# Battery_Management_System.net
KiCad netlist of a schematic drawn in Altium Designer
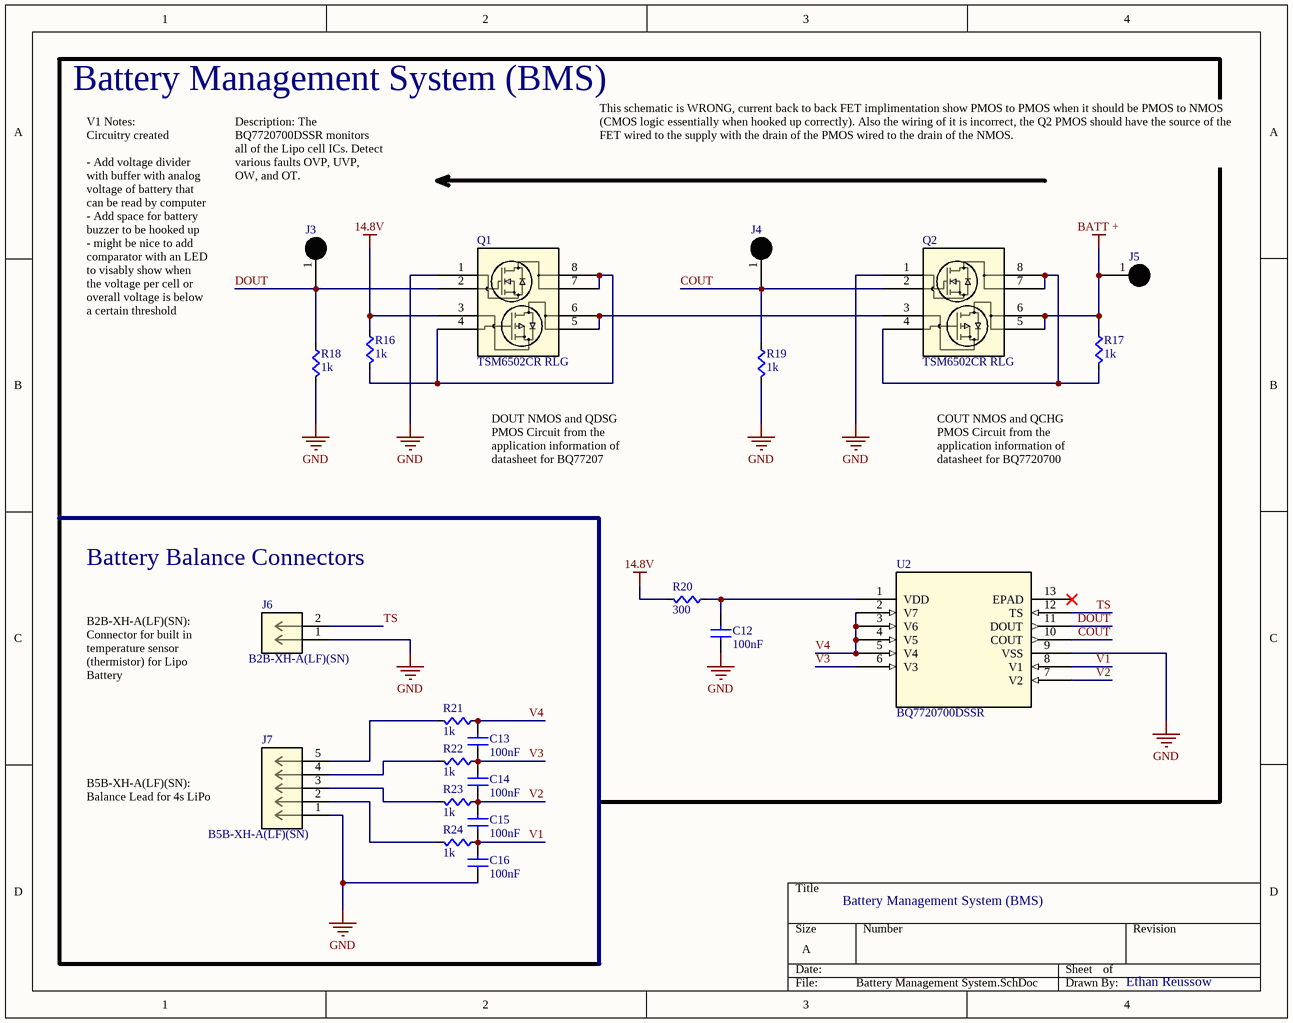
[diagram p0: Battery Management System.SchDoc]

(export (version "E")
  (design (tool "Eeschema 10.0.6"))
  (components
    (comp (ref "C12")
      (value "100nF")
      (footprint "CAPC0603")
      (fields (field (name "Comment") "Cap"))
      (libsource (lib "Passives") (part "Cap"))
    )
    (comp (ref "C13")
      (value "100nF")
      (footprint "CAPC0603")
      (fields (field (name "Comment") "Cap"))
      (libsource (lib "Passives") (part "Cap"))
    )
    (comp (ref "C14")
      (value "100nF")
      (footprint "CAPC0603")
      (fields (field (name "Comment") "Cap"))
      (libsource (lib "Passives") (part "Cap"))
    )
    (comp (ref "C15")
      (value "100nF")
      (footprint "CAPC0603")
      (fields (field (name "Comment") "Cap"))
      (libsource (lib "Passives") (part "Cap"))
    )
    (comp (ref "C16")
      (value "100nF")
      (footprint "CAPC0603")
      (fields (field (name "Comment") "Cap"))
      (libsource (lib "Passives") (part "Cap"))
    )
    (comp (ref "J3")
      (value "5000 Test Point")
      (footprint "5000 Test Point")
      (libsource (lib "Connectors") (part "5000 Test Point"))
    )
    (comp (ref "J4")
      (value "5000 Test Point")
      (footprint "5000 Test Point")
      (libsource (lib "Connectors") (part "5000 Test Point"))
    )
    (comp (ref "J5")
      (value "5000 Test Point")
      (footprint "5000 Test Point")
      (libsource (lib "Connectors") (part "5000 Test Point"))
    )
    (comp (ref "J6")
      (value "B2B-XH-A(LF)(SN)")
      (footprint "CONN_B2B-XH-A(LF)(SN)_JST")
      (description "No Description Available")
      (fields (field (name "COPYRIGHT") "Copyright (C) 2023 Ultra Librarian. All rights reserved."))
      (libsource (lib "Connectors") (part "B2B-XH-A(LF)(SN)"))
    )
    (comp (ref "J7")
      (value "B5B-XH-A(LF)(SN)")
      (footprint "CONN_B5B-XH-A(LF)(SN)_JST")
      (description "No Description Available")
      (fields (field (name "COPYRIGHT") "Copyright (C) 2023 Ultra Librarian. All rights reserved."))
      (libsource (lib "Connectors") (part "B5B-XH-A(LF)(SN)"))
    )
    (comp (ref "Q1")
      (value "TSM6502CR RLG")
      (footprint "PDFN56U_DUAL_TWS")
      (description "No Description Available")
      (fields (field (name "COPYRIGHT") "Copyright (C) 2023 Ultra Librarian. All rights reserved."))
      (libsource (lib "ICs") (part "TSM6502CR RLG"))
    )
    (comp (ref "Q2")
      (value "TSM6502CR RLG")
      (footprint "PDFN56U_DUAL_TWS")
      (description "No Description Available")
      (fields (field (name "COPYRIGHT") "Copyright (C) 2023 Ultra Librarian. All rights reserved."))
      (libsource (lib "ICs") (part "TSM6502CR RLG"))
    )
    (comp (ref "R16")
      (value "1k")
      (footprint "RES0603")
      (fields (field (name "Comment") "Res"))
      (libsource (lib "Passives") (part "Res"))
    )
    (comp (ref "R17")
      (value "1k")
      (footprint "RES0603")
      (fields (field (name "Comment") "Res"))
      (libsource (lib "Passives") (part "Res"))
    )
    (comp (ref "R18")
      (value "1k")
      (footprint "RES0603")
      (fields (field (name "Comment") "Res"))
      (libsource (lib "Passives") (part "Res"))
    )
    (comp (ref "R19")
      (value "1k")
      (footprint "RES0603")
      (fields (field (name "Comment") "Res"))
      (libsource (lib "Passives") (part "Res"))
    )
    (comp (ref "R20")
      (value "300")
      (footprint "RES0603")
      (fields (field (name "Comment") "Res"))
      (libsource (lib "Passives") (part "Res"))
    )
    (comp (ref "R21")
      (value "1k")
      (footprint "RES0603")
      (fields (field (name "Comment") "Res"))
      (libsource (lib "Passives") (part "Res"))
    )
    (comp (ref "R22")
      (value "1k")
      (footprint "RES0603")
      (fields (field (name "Comment") "Res"))
      (libsource (lib "Passives") (part "Res"))
    )
    (comp (ref "R23")
      (value "1k")
      (footprint "RES0603")
      (fields (field (name "Comment") "Res"))
      (libsource (lib "Passives") (part "Res"))
    )
    (comp (ref "R24")
      (value "1k")
      (footprint "RES0603")
      (fields (field (name "Comment") "Res"))
      (libsource (lib "Passives") (part "Res"))
    )
    (comp (ref "U2")
      (value "BQ7720700DSSR")
      (footprint "WSON12_DSS_TEX")
      (description "No Description Available")
      (fields (field (name "COPYRIGHT") "Copyright (C) 2023 Ultra Librarian. All rights reserved."))
      (libsource (lib "ICs") (part "BQ7720700DSSR"))
    )
  )
  (nets
    (net (code "1") (name "/COUT") (class "Default")
      (node (ref "J4") (pin "1") (pintype "passive"))
      (node (ref "Q2") (pin "2") (pinfunction "2_2") (pintype "passive"))
      (node (ref "R19") (pin "2") (pinfunction "B_2") (pintype "passive"))
      (node (ref "U2") (pin "10") (pinfunction "COUT_10") (pintype "output"))
    )
    (net (code "2") (name "/DOUT") (class "Default")
      (node (ref "J3") (pin "1") (pintype "passive"))
      (node (ref "Q1") (pin "2") (pinfunction "2_2") (pintype "passive"))
      (node (ref "R18") (pin "2") (pinfunction "B_2") (pintype "passive"))
      (node (ref "U2") (pin "11") (pinfunction "DOUT_11") (pintype "output"))
    )
    (net (code "3") (name "/TS") (class "Default")
      (node (ref "J6") (pin "2") (pinfunction "2_2") (pintype "passive"))
      (node (ref "U2") (pin "12") (pinfunction "TS_12") (pintype "input"))
    )
    (net (code "4") (name "/V1") (class "Default")
      (node (ref "C15") (pin "2") (pinfunction "B_2") (pintype "passive"))
      (node (ref "C16") (pin "1") (pinfunction "A_1") (pintype "passive"))
      (node (ref "R24") (pin "2") (pinfunction "B_2") (pintype "passive"))
      (node (ref "U2") (pin "8") (pinfunction "V1_8") (pintype "input"))
    )
    (net (code "5") (name "/V2") (class "Default")
      (node (ref "C14") (pin "2") (pinfunction "B_2") (pintype "passive"))
      (node (ref "C15") (pin "1") (pinfunction "A_1") (pintype "passive"))
      (node (ref "R23") (pin "2") (pinfunction "B_2") (pintype "passive"))
      (node (ref "U2") (pin "7") (pinfunction "V2_7") (pintype "input"))
    )
    (net (code "6") (name "/V3") (class "Default")
      (node (ref "C13") (pin "2") (pinfunction "B_2") (pintype "passive"))
      (node (ref "C14") (pin "1") (pinfunction "A_1") (pintype "passive"))
      (node (ref "R22") (pin "2") (pinfunction "B_2") (pintype "passive"))
      (node (ref "U2") (pin "6") (pinfunction "V3_6") (pintype "input"))
    )
    (net (code "7") (name "/V4") (class "Default")
      (node (ref "C13") (pin "1") (pinfunction "A_1") (pintype "passive"))
      (node (ref "R21") (pin "2") (pinfunction "B_2") (pintype "passive"))
      (node (ref "U2") (pin "2") (pinfunction "V7_2") (pintype "input"))
      (node (ref "U2") (pin "3") (pinfunction "V6_3") (pintype "input"))
      (node (ref "U2") (pin "4") (pinfunction "V5_4") (pintype "input"))
      (node (ref "U2") (pin "5") (pinfunction "V4_5") (pintype "input"))
    )
    (net (code "8") (name "14.8V") (class "Default")
      (node (ref "Q1") (pin "3") (pinfunction "3_3") (pintype "passive"))
      (node (ref "R16") (pin "2") (pinfunction "B_2") (pintype "passive"))
      (node (ref "R20") (pin "1") (pinfunction "A_1") (pintype "passive"))
    )
    (net (code "9") (name "BATT +") (class "Default")
      (node (ref "J5") (pin "1") (pintype "passive"))
      (node (ref "Q2") (pin "5") (pinfunction "5_5") (pintype "passive"))
      (node (ref "Q2") (pin "6") (pinfunction "6_6") (pintype "passive"))
      (node (ref "R17") (pin "2") (pinfunction "B_2") (pintype "passive"))
    )
    (net (code "10") (name "GND") (class "Default")
      (node (ref "C12") (pin "2") (pinfunction "B_2") (pintype "passive"))
      (node (ref "C16") (pin "2") (pinfunction "B_2") (pintype "passive"))
      (node (ref "J6") (pin "1") (pinfunction "1_1") (pintype "passive"))
      (node (ref "J7") (pin "1") (pinfunction "1_1") (pintype "passive"))
      (node (ref "Q1") (pin "1") (pinfunction "1_1") (pintype "passive"))
      (node (ref "Q2") (pin "1") (pinfunction "1_1") (pintype "passive"))
      (node (ref "R18") (pin "1") (pinfunction "A_1") (pintype "passive"))
      (node (ref "R19") (pin "1") (pinfunction "A_1") (pintype "passive"))
      (node (ref "U2") (pin "9") (pinfunction "VSS_9") (pintype "passive"))
    )
    (net (code "11") (name "Net-(C12-A)") (class "Default")
      (node (ref "C12") (pin "1") (pinfunction "A_1") (pintype "passive"))
      (node (ref "R20") (pin "2") (pinfunction "B_2") (pintype "passive"))
      (node (ref "U2") (pin "1") (pinfunction "VDD_1") (pintype "power_in"))
    )
    (net (code "12") (name "Net-(Q1-Pad5)") (class "Default")
      (node (ref "Q1") (pin "5") (pinfunction "5_5") (pintype "passive"))
      (node (ref "Q1") (pin "6") (pinfunction "6_6") (pintype "passive"))
      (node (ref "Q2") (pin "3") (pinfunction "3_3") (pintype "passive"))
    )
    (net (code "13") (name "Net-(R16-A)") (class "Default")
      (node (ref "Q1") (pin "4") (pinfunction "4_4") (pintype "passive"))
      (node (ref "Q1") (pin "7") (pinfunction "7_7") (pintype "passive"))
      (node (ref "Q1") (pin "8") (pinfunction "8_8") (pintype "passive"))
      (node (ref "R16") (pin "1") (pinfunction "A_1") (pintype "passive"))
    )
    (net (code "14") (name "Net-(R17-A)") (class "Default")
      (node (ref "Q2") (pin "4") (pinfunction "4_4") (pintype "passive"))
      (node (ref "Q2") (pin "7") (pinfunction "7_7") (pintype "passive"))
      (node (ref "Q2") (pin "8") (pinfunction "8_8") (pintype "passive"))
      (node (ref "R17") (pin "1") (pinfunction "A_1") (pintype "passive"))
    )
    (net (code "15") (name "Net-(R21-A)") (class "Default")
      (node (ref "J7") (pin "5") (pinfunction "5_5") (pintype "passive"))
      (node (ref "R21") (pin "1") (pinfunction "A_1") (pintype "passive"))
    )
    (net (code "16") (name "Net-(R22-A)") (class "Default")
      (node (ref "J7") (pin "4") (pinfunction "4_4") (pintype "passive"))
      (node (ref "R22") (pin "1") (pinfunction "A_1") (pintype "passive"))
    )
    (net (code "17") (name "Net-(R23-A)") (class "Default")
      (node (ref "J7") (pin "3") (pinfunction "3_3") (pintype "passive"))
      (node (ref "R23") (pin "1") (pinfunction "A_1") (pintype "passive"))
    )
    (net (code "18") (name "Net-(R24-A)") (class "Default")
      (node (ref "J7") (pin "2") (pinfunction "2_2") (pintype "passive"))
      (node (ref "R24") (pin "1") (pinfunction "A_1") (pintype "passive"))
    )
    (net (code "19") (name "unconnected-(U2-EPAD-Pad13)") (class "Default")
      (node (ref "U2") (pin "13") (pinfunction "EPAD_13") (pintype "passive+no_connect"))
    )
  )
)
